# Rectification_filter.net
KiCad netlist of a schematic drawn in Altium Designer
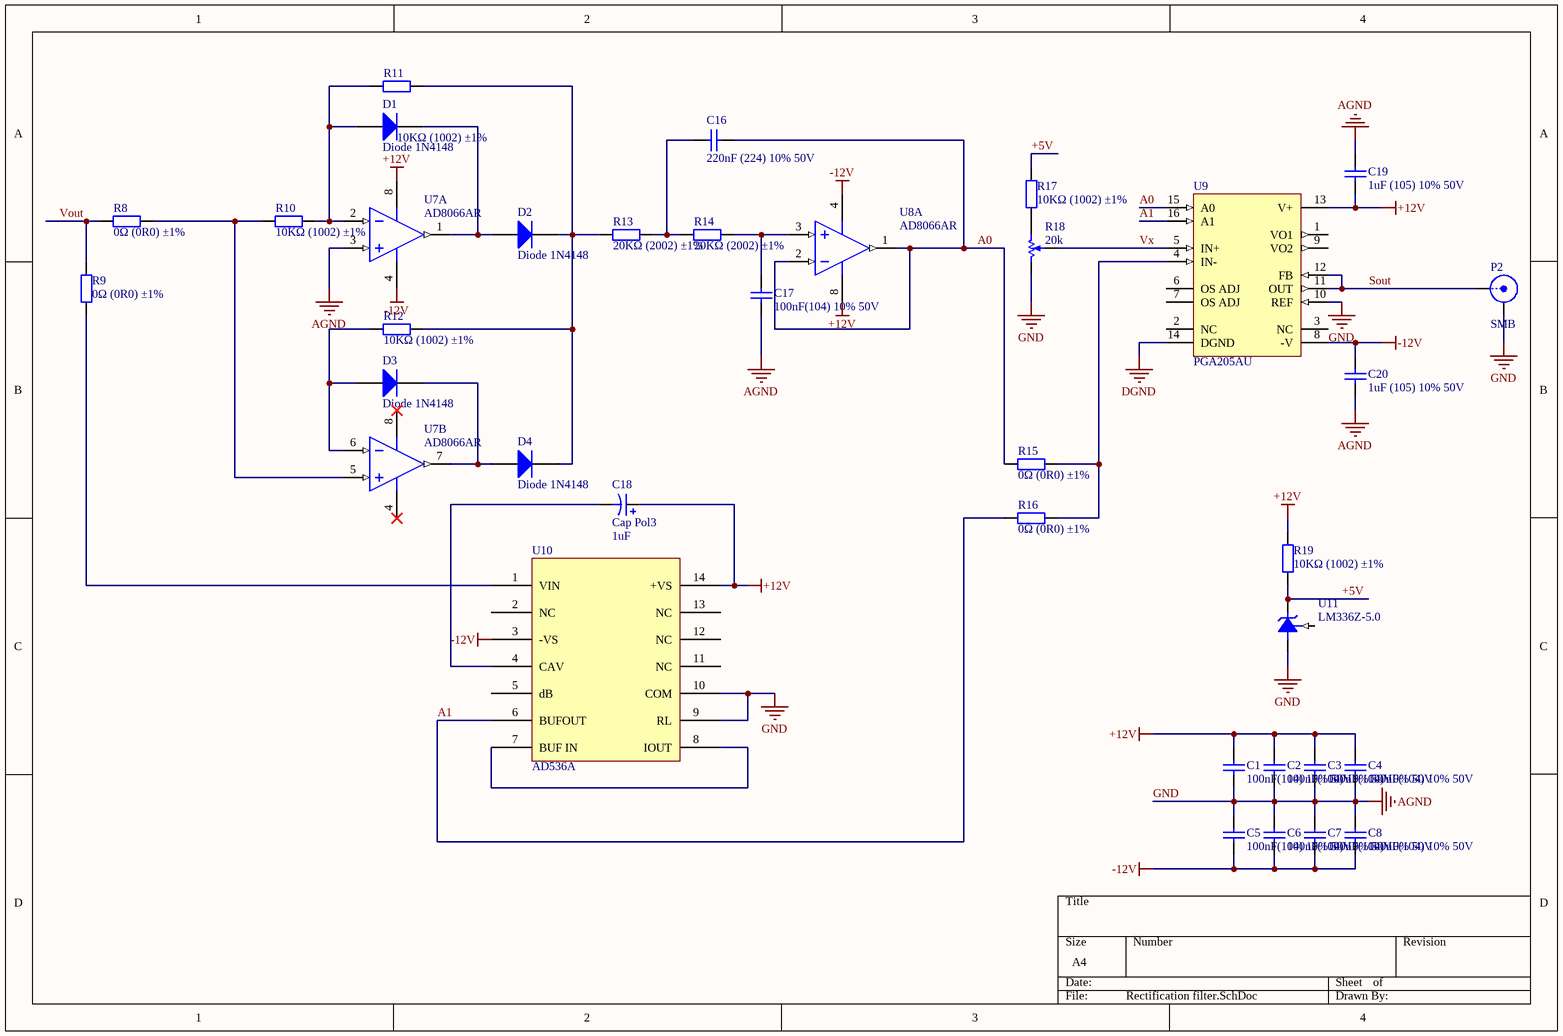
[diagram p0: Rectification filter.SchDoc]

(export (version "E")
  (design (tool "Eeschema 10.0.6"))
  (components
    (comp (ref "20k")
      (value "R18")
      (footprint "POT4MM-2")
      (description "Square Trimming Potentiometer")
      (fields (field (name "PUBLISHER") "Altium Limited"))
      (libsource (lib "Miscellaneous Devices") (part "RPot SM"))
    )
    (comp (ref "C1")
      (value "100nF(104) 10% 50V")
      (footprint "LC-0805_C")
      (description "贴片电容")
      (libsource (lib "Miscellaneous Devices LC") (part "0805 100nF(104) 10% 50V"))
    )
    (comp (ref "C2")
      (value "100nF(104) 10% 50V")
      (footprint "LC-0805_C")
      (description "贴片电容")
      (libsource (lib "Miscellaneous Devices LC") (part "0805 100nF(104) 10% 50V"))
    )
    (comp (ref "C3")
      (value "100nF(104) 10% 50V")
      (footprint "LC-0805_C")
      (description "贴片电容")
      (libsource (lib "Miscellaneous Devices LC") (part "0805 100nF(104) 10% 50V"))
    )
    (comp (ref "C4")
      (value "100nF(104) 10% 50V")
      (footprint "LC-0805_C")
      (description "贴片电容")
      (libsource (lib "Miscellaneous Devices LC") (part "0805 100nF(104) 10% 50V"))
    )
    (comp (ref "C5")
      (value "100nF(104) 10% 50V")
      (footprint "LC-0805_C")
      (description "贴片电容")
      (libsource (lib "Miscellaneous Devices LC") (part "0805 100nF(104) 10% 50V"))
    )
    (comp (ref "C6")
      (value "100nF(104) 10% 50V")
      (footprint "LC-0805_C")
      (description "贴片电容")
      (libsource (lib "Miscellaneous Devices LC") (part "0805 100nF(104) 10% 50V"))
    )
    (comp (ref "C7")
      (value "100nF(104) 10% 50V")
      (footprint "LC-0805_C")
      (description "贴片电容")
      (libsource (lib "Miscellaneous Devices LC") (part "0805 100nF(104) 10% 50V"))
    )
    (comp (ref "C8")
      (value "100nF(104) 10% 50V")
      (footprint "LC-0805_C")
      (description "贴片电容")
      (libsource (lib "Miscellaneous Devices LC") (part "0805 100nF(104) 10% 50V"))
    )
    (comp (ref "C16")
      (value "220nF (224) 10% 50V")
      (footprint "LC-0805_C")
      (description "贴片电容")
      (libsource (lib "Miscellaneous Devices LC") (part "0805 220nF (224) 10% 50V"))
    )
    (comp (ref "C17")
      (value "100nF(104) 10% 50V")
      (footprint "LC-0805_C")
      (description "贴片电容")
      (libsource (lib "Miscellaneous Devices LC") (part "0805 100nF(104) 10% 50V"))
    )
    (comp (ref "C18")
      (value "Cap Pol3")
      (footprint "C0805")
      (description "Polarized Capacitor (Surface Mount)")
      (fields (field (name "ALTIUM_VALUE") "1uF") (field (name "PUBLISHER") "Altium Limited"))
      (libsource (lib "Miscellaneous Devices") (part "Cap Pol3"))
    )
    (comp (ref "C19")
      (value "1uF (105) 10% 50V")
      (footprint "LC-0805_C")
      (description "贴片电容")
      (libsource (lib "Miscellaneous Devices LC") (part "0805 1uF (105) 10% 50V"))
    )
    (comp (ref "C20")
      (value "1uF (105) 10% 50V")
      (footprint "LC-0805_C")
      (description "贴片电容")
      (libsource (lib "Miscellaneous Devices LC") (part "0805 1uF (105) 10% 50V"))
    )
    (comp (ref "D1")
      (value "Diode 1N4148")
      (footprint "DO-35")
      (description "High Conductance Fast Diode")
      (fields (field (name "PUBLISHER") "Altium Limited"))
      (libsource (lib "Miscellaneous Devices") (part "Diode 1N4148"))
    )
    (comp (ref "D2")
      (value "Diode 1N4148")
      (footprint "DO-35")
      (description "High Conductance Fast Diode")
      (fields (field (name "PUBLISHER") "Altium Limited"))
      (libsource (lib "Miscellaneous Devices") (part "Diode 1N4148"))
    )
    (comp (ref "D3")
      (value "Diode 1N4148")
      (footprint "DO-35")
      (description "High Conductance Fast Diode")
      (fields (field (name "PUBLISHER") "Altium Limited"))
      (libsource (lib "Miscellaneous Devices") (part "Diode 1N4148"))
    )
    (comp (ref "D4")
      (value "Diode 1N4148")
      (footprint "DO-35")
      (description "High Conductance Fast Diode")
      (fields (field (name "PUBLISHER") "Altium Limited"))
      (libsource (lib "Miscellaneous Devices") (part "Diode 1N4148"))
    )
    (comp (ref "P2")
      (value "SMB")
      (footprint "SMB_V-RJ45")
      (description "SMB Straight Connector")
      (fields (field (name "PUBLISHER") "Altium Limited"))
      (libsource (lib "Miscellaneous Connectors") (part "SMB"))
    )
    (comp (ref "R8")
      (value "0Ω (0R0) ±1%")
      (footprint "LC-0805_R")
      (description "贴片电阻")
      (libsource (lib "Miscellaneous Devices LC") (part "0805 0Ω (0R0) 1%"))
    )
    (comp (ref "R9")
      (value "0Ω (0R0) ±1%")
      (footprint "LC-0805_R")
      (description "贴片电阻")
      (libsource (lib "") (part "0805 0Ω (0R0) 1%_1"))
    )
    (comp (ref "R10")
      (value "10KΩ (1002) ±1%")
      (footprint "LC-0805_R")
      (description "贴片电阻")
      (libsource (lib "Miscellaneous Devices LC") (part "0805 10KΩ (1002) 1%"))
    )
    (comp (ref "R11")
      (value "10KΩ (1002) ±1%")
      (footprint "LC-0805_R")
      (description "贴片电阻")
      (libsource (lib "Miscellaneous Devices LC") (part "0805 10KΩ (1002) 1%"))
    )
    (comp (ref "R12")
      (value "10KΩ (1002) ±1%")
      (footprint "LC-0805_R")
      (description "贴片电阻")
      (libsource (lib "Miscellaneous Devices LC") (part "0805 10KΩ (1002) 1%"))
    )
    (comp (ref "R13")
      (value "20KΩ (2002) ±1%")
      (footprint "LC-0805_R")
      (description "贴片电阻")
      (libsource (lib "Miscellaneous Devices LC") (part "0805 20KΩ (2002) 1%"))
    )
    (comp (ref "R14")
      (value "20KΩ (2002) ±1%")
      (footprint "LC-0805_R")
      (description "贴片电阻")
      (libsource (lib "Miscellaneous Devices LC") (part "0805 20KΩ (2002) 1%"))
    )
    (comp (ref "R15")
      (value "0Ω (0R0) ±1%")
      (footprint "LC-0805_R")
      (description "贴片电阻")
      (libsource (lib "Miscellaneous Devices LC") (part "0805 0Ω (0R0) 1%"))
    )
    (comp (ref "R16")
      (value "0Ω (0R0) ±1%")
      (footprint "LC-0805_R")
      (description "贴片电阻")
      (libsource (lib "Miscellaneous Devices LC") (part "0805 0Ω (0R0) 1%"))
    )
    (comp (ref "R17")
      (value "10KΩ (1002) ±1%")
      (footprint "LC-0805_R")
      (description "贴片电阻")
      (libsource (lib "Miscellaneous Devices LC") (part "0805 10KΩ (1002) 1%"))
    )
    (comp (ref "R19")
      (value "10KΩ (1002) ±1%")
      (footprint "LC-0805_R")
      (description "贴片电阻")
      (libsource (lib "") (part "0805 10KΩ (1002) 1%_1"))
    )
    (comp (ref "U7")
      (value "AD8066AR")
      (footprint "ADI-R-8_N")
      (fields (field (name "GENERIC PART NUMBER") "AD8066") (field (name "MANUFACTURER") "Analog Devices"))
      (libsource (lib "Analog Devices Operational Amplifiers") (part "AD8066AR"))
    )
    (comp (ref "U8")
      (value "AD8066AR")
      (footprint "ADI-R-8_N")
      (fields (field (name "GENERIC PART NUMBER") "AD8066") (field (name "MANUFACTURER") "Analog Devices"))
      (libsource (lib "Analog Devices Operational Amplifiers") (part "AD8066AR"))
    )
    (comp (ref "U9")
      (value "PGA205AU")
      (footprint "211F_N")
      (description "Programmable Gain Instrumentation Amplifier")
      (fields (field (name "PUBLISHER") "Altium Limited"))
      (libsource (lib "BB Instrumentation Amplifier") (part "PGA205AU"))
    )
    (comp (ref "U10") (value "AD536A") (libsource (lib "AD536A") (part "AD536A")))
    (comp (ref "U11")
      (value "LM336Z-5.0")
      (footprint "Z03A")
      (description "5.0V Reference Diode, 3-pin TO-92")
      (fields
        (field (name "MANUFACTURER") "National Semiconductor")
        (field (name "PUBLISHER") "Altium Limited")
      )
      (libsource (lib "NSC Voltage Reference") (part "LM336Z-5.0"))
    )
  )
  (nets
    (net (code "1") (name "+12V") (class "Default")
      (node (ref "C1") (pin "2") (pinfunction "2_2") (pintype "passive"))
      (node (ref "C18") (pin "1") (pinfunction "1_1") (pintype "passive"))
      (node (ref "C19") (pin "1") (pinfunction "1_1") (pintype "passive"))
      (node (ref "C2") (pin "2") (pinfunction "2_2") (pintype "passive"))
      (node (ref "C3") (pin "2") (pinfunction "2_2") (pintype "passive"))
      (node (ref "C4") (pin "2") (pinfunction "2_2") (pintype "passive"))
      (node (ref "R19") (pin "2") (pinfunction "2_2") (pintype "passive"))
      (node (ref "U10") (pin "14") (pinfunction "+VS_14") (pintype "passive"))
      (node (ref "U7") (pin "8") (pinfunction "+VS_8") (pintype "power_in"))
      (node (ref "U8") (pin "8") (pinfunction "+VS_8") (pintype "power_in"))
      (node (ref "U9") (pin "13") (pinfunction "V+_13") (pintype "power_in"))
    )
    (net (code "2") (name "-12V") (class "Default")
      (node (ref "C20") (pin "2") (pinfunction "2_2") (pintype "passive"))
      (node (ref "C5") (pin "1") (pinfunction "1_1") (pintype "passive"))
      (node (ref "C6") (pin "1") (pinfunction "1_1") (pintype "passive"))
      (node (ref "C7") (pin "1") (pinfunction "1_1") (pintype "passive"))
      (node (ref "C8") (pin "1") (pinfunction "1_1") (pintype "passive"))
      (node (ref "U10") (pin "3") (pinfunction "-VS_3") (pintype "passive"))
      (node (ref "U7") (pin "4") (pinfunction "-VS_4") (pintype "power_in"))
      (node (ref "U8") (pin "4") (pinfunction "-VS_4") (pintype "power_in"))
      (node (ref "U9") (pin "8") (pinfunction "-V_8") (pintype "power_in"))
    )
    (net (code "3") (name "/+5V") (class "Default")
      (node (ref "R17") (pin "2") (pinfunction "2_2") (pintype "passive"))
      (node (ref "R19") (pin "1") (pinfunction "1_1") (pintype "passive"))
      (node (ref "U11") (pin "2") (pinfunction "+V_2") (pintype "passive"))
    )
    (net (code "4") (name "/A0") (class "Default")
      (node (ref "C16") (pin "2") (pinfunction "2_2") (pintype "passive"))
      (node (ref "R15") (pin "1") (pinfunction "1_1") (pintype "passive"))
      (node (ref "U8") (pin "1") (pinfunction "VOUT_1_1") (pintype "output"))
      (node (ref "U8") (pin "2") (pinfunction "-IN_1_2") (pintype "input"))
      (node (ref "U9") (pin "15") (pinfunction "A0_15") (pintype "input"))
    )
    (net (code "5") (name "/A1") (class "Default")
      (node (ref "R16") (pin "1") (pinfunction "1_1") (pintype "passive"))
      (node (ref "U10") (pin "6") (pinfunction "BUFOUT_6") (pintype "passive"))
      (node (ref "U9") (pin "16") (pinfunction "A1_16") (pintype "input"))
    )
    (net (code "6") (name "/Sout") (class "Default")
      (node (ref "P2") (pin "1") (pinfunction "X_1") (pintype "passive"))
      (node (ref "U9") (pin "11") (pinfunction "OUT_11") (pintype "output"))
      (node (ref "U9") (pin "12") (pinfunction "FB_12") (pintype "input"))
    )
    (net (code "7") (name "/Vout") (class "Default")
      (node (ref "R8") (pin "1") (pinfunction "1_1") (pintype "passive"))
      (node (ref "R9") (pin "2") (pinfunction "2_2") (pintype "passive"))
    )
    (net (code "8") (name "/Vx") (class "Default")
      (node (ref "20k") (pin "W") (pinfunction "W_W") (pintype "passive"))
      (node (ref "U9") (pin "5") (pinfunction "IN+_5") (pintype "input"))
    )
    (net (code "9") (name "AGND") (class "Default")
      (node (ref "20k") (pin "CW") (pinfunction "+_CW") (pintype "passive"))
      (node (ref "C1") (pin "1") (pinfunction "1_1") (pintype "passive"))
      (node (ref "C17") (pin "1") (pinfunction "1_1") (pintype "passive"))
      (node (ref "C19") (pin "2") (pinfunction "2_2") (pintype "passive"))
      (node (ref "C2") (pin "1") (pinfunction "1_1") (pintype "passive"))
      (node (ref "C20") (pin "1") (pinfunction "1_1") (pintype "passive"))
      (node (ref "C3") (pin "1") (pinfunction "1_1") (pintype "passive"))
      (node (ref "C4") (pin "1") (pinfunction "1_1") (pintype "passive"))
      (node (ref "C5") (pin "2") (pinfunction "2_2") (pintype "passive"))
      (node (ref "C6") (pin "2") (pinfunction "2_2") (pintype "passive"))
      (node (ref "C7") (pin "2") (pinfunction "2_2") (pintype "passive"))
      (node (ref "C8") (pin "2") (pinfunction "2_2") (pintype "passive"))
      (node (ref "P2") (pin "2") (pinfunction "Y_2") (pintype "passive"))
      (node (ref "U10") (pin "10") (pinfunction "COM_10") (pintype "passive"))
      (node (ref "U10") (pin "9") (pinfunction "RL_9") (pintype "passive"))
      (node (ref "U11") (pin "3") (pinfunction "-V_3") (pintype "passive"))
      (node (ref "U7") (pin "3") (pinfunction "+IN_1_3") (pintype "input"))
      (node (ref "U9") (pin "10") (pinfunction "REF_10") (pintype "input"))
    )
    (net (code "10") (name "DGND") (class "Default")
      (node (ref "U9") (pin "14") (pinfunction "DGND_14") (pintype "power_in"))
    )
    (net (code "11") (name "Net-(20k--)") (class "Default")
      (node (ref "20k") (pin "CCW") (pinfunction "-_CCW") (pintype "passive"))
      (node (ref "R17") (pin "1") (pinfunction "1_1") (pintype "passive"))
    )
    (net (code "12") (name "Net-(C16-Pad1)") (class "Default")
      (node (ref "C16") (pin "1") (pinfunction "1_1") (pintype "passive"))
      (node (ref "R13") (pin "2") (pinfunction "2_2") (pintype "passive"))
      (node (ref "R14") (pin "1") (pinfunction "1_1") (pintype "passive"))
    )
    (net (code "13") (name "Net-(D1-A)") (class "Default")
      (node (ref "D1") (pin "1") (pinfunction "A_1") (pintype "passive"))
      (node (ref "R10") (pin "2") (pinfunction "2_2") (pintype "passive"))
      (node (ref "R11") (pin "1") (pinfunction "1_1") (pintype "passive"))
      (node (ref "U7") (pin "2") (pinfunction "-IN_1_2") (pintype "input"))
    )
    (net (code "14") (name "Net-(D1-K)") (class "Default")
      (node (ref "D1") (pin "2") (pinfunction "K_2") (pintype "passive"))
      (node (ref "D2") (pin "1") (pinfunction "A_1") (pintype "passive"))
      (node (ref "U7") (pin "1") (pinfunction "VOUT_1_1") (pintype "output"))
    )
    (net (code "15") (name "Net-(D2-K)") (class "Default")
      (node (ref "D2") (pin "2") (pinfunction "K_2") (pintype "passive"))
      (node (ref "D4") (pin "2") (pinfunction "K_2") (pintype "passive"))
      (node (ref "R11") (pin "2") (pinfunction "2_2") (pintype "passive"))
      (node (ref "R12") (pin "2") (pinfunction "2_2") (pintype "passive"))
      (node (ref "R13") (pin "1") (pinfunction "1_1") (pintype "passive"))
    )
    (net (code "16") (name "Net-(D3-A)") (class "Default")
      (node (ref "D3") (pin "1") (pinfunction "A_1") (pintype "passive"))
      (node (ref "R12") (pin "1") (pinfunction "1_1") (pintype "passive"))
      (node (ref "U7") (pin "6") (pinfunction "-IN_2_6") (pintype "input"))
    )
    (net (code "17") (name "Net-(D3-K)") (class "Default")
      (node (ref "D3") (pin "2") (pinfunction "K_2") (pintype "passive"))
      (node (ref "D4") (pin "1") (pinfunction "A_1") (pintype "passive"))
      (node (ref "U7") (pin "7") (pinfunction "VOUT_2_7") (pintype "output"))
    )
    (net (code "18") (name "Net-(U7B-+IN_2)") (class "Default")
      (node (ref "R10") (pin "1") (pinfunction "1_1") (pintype "passive"))
      (node (ref "R8") (pin "2") (pinfunction "2_2") (pintype "passive"))
      (node (ref "U7") (pin "5") (pinfunction "+IN_2_5") (pintype "input"))
    )
    (net (code "19") (name "Net-(U8A-+IN_1)") (class "Default")
      (node (ref "C17") (pin "2") (pinfunction "2_2") (pintype "passive"))
      (node (ref "R14") (pin "2") (pinfunction "2_2") (pintype "passive"))
      (node (ref "U8") (pin "3") (pinfunction "+IN_1_3") (pintype "input"))
    )
    (net (code "20") (name "Net-(U9-IN-)") (class "Default")
      (node (ref "R15") (pin "2") (pinfunction "2_2") (pintype "passive"))
      (node (ref "R16") (pin "2") (pinfunction "2_2") (pintype "passive"))
      (node (ref "U9") (pin "4") (pinfunction "IN-_4") (pintype "input"))
    )
    (net (code "21") (name "Net-(U10-BUF_IN)") (class "Default")
      (node (ref "U10") (pin "7") (pinfunction "BUF_IN_7") (pintype "passive"))
      (node (ref "U10") (pin "8") (pinfunction "IOUT_8") (pintype "passive"))
    )
    (net (code "22") (name "Net-(U10-CAV)") (class "Default")
      (node (ref "C18") (pin "2") (pinfunction "2_2") (pintype "passive"))
      (node (ref "U10") (pin "4") (pinfunction "CAV_4") (pintype "passive"))
    )
    (net (code "23") (name "Net-(U10-VIN)") (class "Default")
      (node (ref "R9") (pin "1") (pinfunction "1_1") (pintype "passive"))
      (node (ref "U10") (pin "1") (pinfunction "VIN_1") (pintype "passive"))
    )
    (net (code "24") (name "unconnected-(U7B-+VS-Pad8)") (class "Default")
      (node (ref "U7") (pin "8") (pinfunction "+VS_8") (pintype "power_in+no_connect"))
    )
    (net (code "25") (name "unconnected-(U7B--VS-Pad4)") (class "Default")
      (node (ref "U7") (pin "4") (pinfunction "-VS_4") (pintype "power_in+no_connect"))
    )
    (net (code "26") (name "unconnected-(U9-NC-Pad2)") (class "Default")
      (node (ref "U9") (pin "2") (pinfunction "NC_2") (pintype "passive"))
    )
    (net (code "27") (name "unconnected-(U9-NC-Pad3)") (class "Default")
      (node (ref "U9") (pin "3") (pinfunction "NC_3") (pintype "passive"))
    )
    (net (code "28") (name "unconnected-(U9-OS_ADJ-Pad6)") (class "Default")
      (node (ref "U9") (pin "6") (pinfunction "OS_ADJ_6") (pintype "passive"))
    )
    (net (code "29") (name "unconnected-(U9-OS_ADJ-Pad7)") (class "Default")
      (node (ref "U9") (pin "7") (pinfunction "OS_ADJ_7") (pintype "passive"))
    )
    (net (code "30") (name "unconnected-(U9-VO1-Pad1)") (class "Default")
      (node (ref "U9") (pin "1") (pinfunction "VO1_1") (pintype "output"))
    )
    (net (code "31") (name "unconnected-(U9-VO2-Pad9)") (class "Default")
      (node (ref "U9") (pin "9") (pinfunction "VO2_9") (pintype "output"))
    )
    (net (code "32") (name "unconnected-(U10-NC-Pad2)") (class "Default")
      (node (ref "U10") (pin "2") (pinfunction "NC_2") (pintype "passive"))
    )
    (net (code "33") (name "unconnected-(U10-NC-Pad11)") (class "Default")
      (node (ref "U10") (pin "11") (pinfunction "NC_11") (pintype "passive"))
    )
    (net (code "34") (name "unconnected-(U10-NC-Pad12)") (class "Default")
      (node (ref "U10") (pin "12") (pinfunction "NC_12") (pintype "passive"))
    )
    (net (code "35") (name "unconnected-(U10-NC-Pad13)") (class "Default")
      (node (ref "U10") (pin "13") (pinfunction "NC_13") (pintype "passive"))
    )
    (net (code "36") (name "unconnected-(U10-dB-Pad5)") (class "Default")
      (node (ref "U10") (pin "5") (pinfunction "dB_5") (pintype "passive"))
    )
    (net (code "37") (name "unconnected-(U11-ADJ-Pad1)") (class "Default")
      (node (ref "U11") (pin "1") (pinfunction "ADJ_1") (pintype "input"))
    )
  )
)
